# bga_test.net
KiCad netlist of a schematic drawn in EAGLE
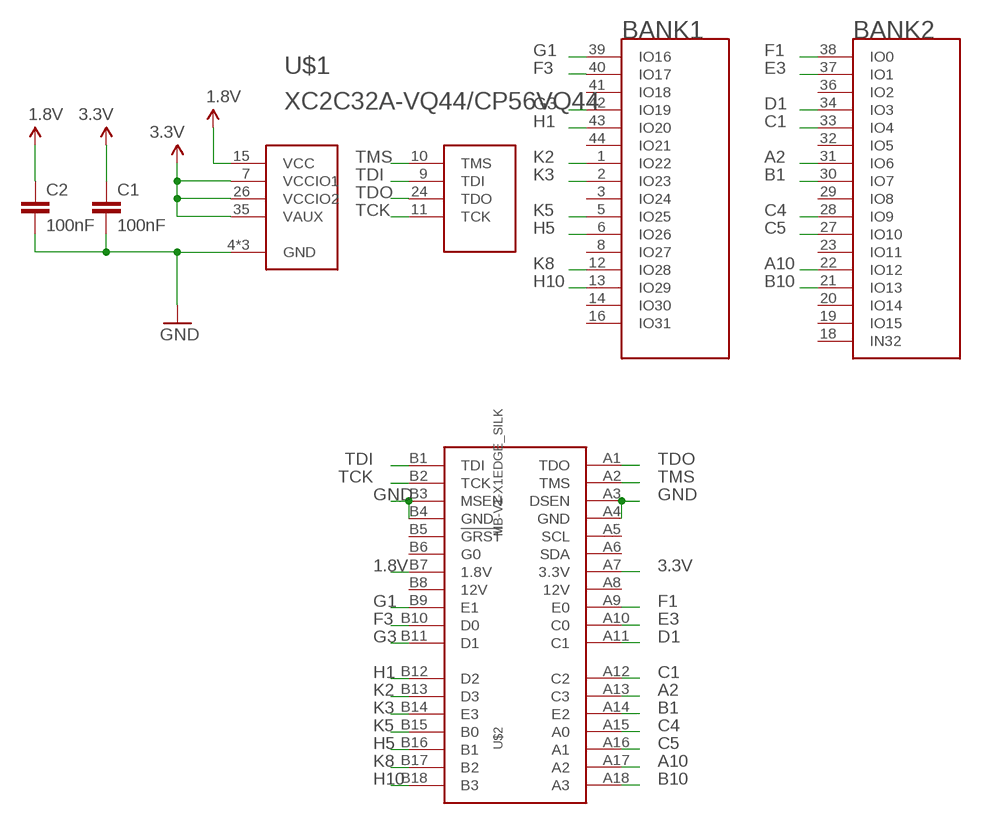
[diagram p0: schematic, sheet 1]

(export (version "E")
  (design (tool "Eeschema 10.0.6"))
  (components
    (comp (ref "C1")
      (value "100nF")
      (footprint "eagle-import:0402-CAP")
      (libsource (lib "eagle-import") (part "CAP0402-CAP"))
    )
    (comp (ref "C2")
      (value "100nF")
      (footprint "eagle-import:0402-CAP")
      (libsource (lib "eagle-import") (part "CAP0402-CAP"))
    )
    (comp (ref "U$1")
      (value "XC2C32A-VQ44/CP56VQ44")
      (footprint "eagle-import:XILINX_VQ44")
      (libsource (lib "eagle-import") (part "XC2C32A-VQ44/CP56VQ44"))
    )
    (comp (ref "U$2")
      (value "MB-V1-X1EDGE_SILK")
      (footprint "eagle-import:MB-V1-X1-EDGE")
      (libsource (lib "eagle-import") (part "MB-V1-X1EDGE_SILK"))
    )
  )
  (nets
    (net (code "1") (name "/A2") (class "Default")
      (node (ref "U$1") (pin "31") (pinfunction "IO6_31") (pintype "bidirectional"))
      (node (ref "U$2") (pin "A13") (pinfunction "C3_A13") (pintype "bidirectional"))
    )
    (net (code "2") (name "/A10") (class "Default")
      (node (ref "U$1") (pin "22") (pinfunction "IO12_22") (pintype "bidirectional"))
      (node (ref "U$2") (pin "A17") (pinfunction "A2_A17") (pintype "bidirectional"))
    )
    (net (code "3") (name "/B1") (class "Default")
      (node (ref "U$1") (pin "30") (pinfunction "IO7_30") (pintype "bidirectional"))
      (node (ref "U$2") (pin "A14") (pinfunction "E2_A14") (pintype "bidirectional"))
    )
    (net (code "4") (name "/B10") (class "Default")
      (node (ref "U$1") (pin "21") (pinfunction "IO13_21") (pintype "bidirectional"))
      (node (ref "U$2") (pin "A18") (pinfunction "A3_A18") (pintype "bidirectional"))
    )
    (net (code "5") (name "/C1") (class "Default")
      (node (ref "U$1") (pin "33") (pinfunction "IO4_33") (pintype "bidirectional"))
      (node (ref "U$2") (pin "A12") (pinfunction "C2_A12") (pintype "bidirectional"))
    )
    (net (code "6") (name "/C4") (class "Default")
      (node (ref "U$1") (pin "28") (pinfunction "IO9_28") (pintype "bidirectional"))
      (node (ref "U$2") (pin "A15") (pinfunction "A0_A15") (pintype "bidirectional"))
    )
    (net (code "7") (name "/C5") (class "Default")
      (node (ref "U$1") (pin "27") (pinfunction "IO10_27") (pintype "bidirectional"))
      (node (ref "U$2") (pin "A16") (pinfunction "A1_A16") (pintype "bidirectional"))
    )
    (net (code "8") (name "/D1") (class "Default")
      (node (ref "U$1") (pin "34") (pinfunction "IO3_34") (pintype "bidirectional"))
      (node (ref "U$2") (pin "A11") (pinfunction "C1_A11") (pintype "bidirectional"))
    )
    (net (code "9") (name "/E3") (class "Default")
      (node (ref "U$1") (pin "37") (pinfunction "IO1_37") (pintype "bidirectional"))
      (node (ref "U$2") (pin "A10") (pinfunction "C0_A10") (pintype "bidirectional"))
    )
    (net (code "10") (name "/F1") (class "Default")
      (node (ref "U$1") (pin "38") (pinfunction "IO0_38") (pintype "bidirectional"))
      (node (ref "U$2") (pin "A9") (pinfunction "E0_A9") (pintype "bidirectional"))
    )
    (net (code "11") (name "/F3") (class "Default")
      (node (ref "U$1") (pin "40") (pinfunction "IO17_40") (pintype "bidirectional"))
      (node (ref "U$2") (pin "B10") (pinfunction "D0_B10") (pintype "bidirectional"))
    )
    (net (code "12") (name "/G1") (class "Default")
      (node (ref "U$1") (pin "39") (pinfunction "IO16_39") (pintype "bidirectional"))
      (node (ref "U$2") (pin "B9") (pinfunction "E1_B9") (pintype "bidirectional"))
    )
    (net (code "13") (name "/G3") (class "Default")
      (node (ref "U$1") (pin "42") (pinfunction "IO19_42") (pintype "bidirectional"))
      (node (ref "U$2") (pin "B11") (pinfunction "D1_B11") (pintype "bidirectional"))
    )
    (net (code "14") (name "/H1") (class "Default")
      (node (ref "U$1") (pin "43") (pinfunction "IO20_43") (pintype "bidirectional"))
      (node (ref "U$2") (pin "B12") (pinfunction "D2_B12") (pintype "bidirectional"))
    )
    (net (code "15") (name "/H5") (class "Default")
      (node (ref "U$1") (pin "6") (pinfunction "IO26_6") (pintype "bidirectional"))
      (node (ref "U$2") (pin "B16") (pinfunction "B1_B16") (pintype "bidirectional"))
    )
    (net (code "16") (name "/H10") (class "Default")
      (node (ref "U$1") (pin "13") (pinfunction "IO29_13") (pintype "bidirectional"))
      (node (ref "U$2") (pin "B18") (pinfunction "B3_B18") (pintype "bidirectional"))
    )
    (net (code "17") (name "/K2") (class "Default")
      (node (ref "U$1") (pin "1") (pinfunction "IO22_1") (pintype "bidirectional"))
      (node (ref "U$2") (pin "B13") (pinfunction "D3_B13") (pintype "bidirectional"))
    )
    (net (code "18") (name "/K3") (class "Default")
      (node (ref "U$1") (pin "2") (pinfunction "IO23_2") (pintype "bidirectional"))
      (node (ref "U$2") (pin "B14") (pinfunction "E3_B14") (pintype "bidirectional"))
    )
    (net (code "19") (name "/K5") (class "Default")
      (node (ref "U$1") (pin "5") (pinfunction "IO25_5") (pintype "bidirectional"))
      (node (ref "U$2") (pin "B15") (pinfunction "B0_B15") (pintype "bidirectional"))
    )
    (net (code "20") (name "/K8") (class "Default")
      (node (ref "U$1") (pin "12") (pinfunction "IO28_12") (pintype "bidirectional"))
      (node (ref "U$2") (pin "B17") (pinfunction "B2_B17") (pintype "bidirectional"))
    )
    (net (code "21") (name "/TCK") (class "Default")
      (node (ref "U$1") (pin "11") (pinfunction "TCK_11") (pintype "bidirectional"))
      (node (ref "U$2") (pin "B2") (pinfunction "TCK_B2") (pintype "bidirectional"))
    )
    (net (code "22") (name "/TDI") (class "Default")
      (node (ref "U$1") (pin "9") (pinfunction "TDI_9") (pintype "bidirectional"))
      (node (ref "U$2") (pin "B1") (pinfunction "TDI_B1") (pintype "bidirectional"))
    )
    (net (code "23") (name "/TDO") (class "Default")
      (node (ref "U$1") (pin "24") (pinfunction "TDO_24") (pintype "bidirectional"))
      (node (ref "U$2") (pin "A1") (pinfunction "TDO_A1") (pintype "bidirectional"))
    )
    (net (code "24") (name "/TMS") (class "Default")
      (node (ref "U$1") (pin "10") (pinfunction "TMS_10") (pintype "bidirectional"))
      (node (ref "U$2") (pin "A2") (pinfunction "TMS_A2") (pintype "bidirectional"))
    )
    (net (code "25") (name "1.8V") (class "Default")
      (node (ref "C2") (pin "1") (pinfunction "1_1") (pintype "passive"))
      (node (ref "U$1") (pin "15") (pinfunction "VCC_15") (pintype "bidirectional"))
      (node (ref "U$2") (pin "B7") (pinfunction "1.8V_B7") (pintype "bidirectional"))
    )
    (net (code "26") (name "3.3V") (class "Default")
      (node (ref "C1") (pin "1") (pinfunction "1_1") (pintype "passive"))
      (node (ref "U$1") (pin "26") (pinfunction "VCCIO2_26") (pintype "bidirectional"))
      (node (ref "U$1") (pin "35") (pinfunction "VAUX_35") (pintype "bidirectional"))
      (node (ref "U$1") (pin "7") (pinfunction "VCCIO1_7") (pintype "bidirectional"))
      (node (ref "U$2") (pin "A7") (pinfunction "3.3V_A7") (pintype "bidirectional"))
    )
    (net (code "27") (name "GND") (class "Default")
      (node (ref "C1") (pin "2") (pinfunction "2_2") (pintype "passive"))
      (node (ref "C2") (pin "2") (pinfunction "2_2") (pintype "passive"))
      (node (ref "U$1") (pin "17") (pinfunction "GND_17") (pintype "bidirectional"))
      (node (ref "U$1") (pin "25") (pinfunction "GND_25") (pintype "bidirectional"))
      (node (ref "U$1") (pin "4") (pinfunction "GND_4") (pintype "bidirectional"))
      (node (ref "U$2") (pin "A3") (pinfunction "DSEN_A3") (pintype "bidirectional"))
      (node (ref "U$2") (pin "A4") (pinfunction "GND_A4") (pintype "bidirectional"))
      (node (ref "U$2") (pin "B3") (pinfunction "MSEN_B3") (pintype "bidirectional"))
      (node (ref "U$2") (pin "B4") (pinfunction "GND_B4") (pintype "bidirectional"))
    )
    (net (code "28") (name "unconnected-(U$1-IN32-Pad18)") (class "Default")
      (node (ref "U$1") (pin "18") (pinfunction "IN32_18") (pintype "bidirectional"))
    )
    (net (code "29") (name "unconnected-(U$1-IO2-Pad36)") (class "Default")
      (node (ref "U$1") (pin "36") (pinfunction "IO2_36") (pintype "bidirectional"))
    )
    (net (code "30") (name "unconnected-(U$1-IO5-Pad32)") (class "Default")
      (node (ref "U$1") (pin "32") (pinfunction "IO5_32") (pintype "bidirectional"))
    )
    (net (code "31") (name "unconnected-(U$1-IO8-Pad29)") (class "Default")
      (node (ref "U$1") (pin "29") (pinfunction "IO8_29") (pintype "bidirectional"))
    )
    (net (code "32") (name "unconnected-(U$1-IO11-Pad23)") (class "Default")
      (node (ref "U$1") (pin "23") (pinfunction "IO11_23") (pintype "bidirectional"))
    )
    (net (code "33") (name "unconnected-(U$1-IO14-Pad20)") (class "Default")
      (node (ref "U$1") (pin "20") (pinfunction "IO14_20") (pintype "bidirectional"))
    )
    (net (code "34") (name "unconnected-(U$1-IO15-Pad19)") (class "Default")
      (node (ref "U$1") (pin "19") (pinfunction "IO15_19") (pintype "bidirectional"))
    )
    (net (code "35") (name "unconnected-(U$1-IO18-Pad41)") (class "Default")
      (node (ref "U$1") (pin "41") (pinfunction "IO18_41") (pintype "bidirectional"))
    )
    (net (code "36") (name "unconnected-(U$1-IO21-Pad44)") (class "Default")
      (node (ref "U$1") (pin "44") (pinfunction "IO21_44") (pintype "bidirectional"))
    )
    (net (code "37") (name "unconnected-(U$1-IO24-Pad3)") (class "Default")
      (node (ref "U$1") (pin "3") (pinfunction "IO24_3") (pintype "bidirectional"))
    )
    (net (code "38") (name "unconnected-(U$1-IO27-Pad8)") (class "Default")
      (node (ref "U$1") (pin "8") (pinfunction "IO27_8") (pintype "bidirectional"))
    )
    (net (code "39") (name "unconnected-(U$1-IO30-Pad14)") (class "Default")
      (node (ref "U$1") (pin "14") (pinfunction "IO30_14") (pintype "bidirectional"))
    )
    (net (code "40") (name "unconnected-(U$1-IO31-Pad16)") (class "Default")
      (node (ref "U$1") (pin "16") (pinfunction "IO31_16") (pintype "bidirectional"))
    )
    (net (code "41") (name "unconnected-(U$2-12V-PadA8)") (class "Default")
      (node (ref "U$2") (pin "A8") (pinfunction "12V_A8") (pintype "bidirectional"))
    )
    (net (code "42") (name "unconnected-(U$2-12V-PadB8)") (class "Default")
      (node (ref "U$2") (pin "B8") (pinfunction "12V_B8") (pintype "bidirectional"))
    )
    (net (code "43") (name "unconnected-(U$2-G0-PadB6)") (class "Default")
      (node (ref "U$2") (pin "B6") (pinfunction "G0_B6") (pintype "bidirectional"))
    )
    (net (code "44") (name "unconnected-(U$2-SCL-PadA5)") (class "Default")
      (node (ref "U$2") (pin "A5") (pinfunction "SCL_A5") (pintype "bidirectional"))
    )
    (net (code "45") (name "unconnected-(U$2-SDA-PadA6)") (class "Default")
      (node (ref "U$2") (pin "A6") (pinfunction "SDA_A6") (pintype "bidirectional"))
    )
    (net (code "46") (name "unconnected-(U$2-~{GRST}-PadB5)") (class "Default")
      (node (ref "U$2") (pin "B5") (pinfunction "~{GRST}_B5") (pintype "bidirectional"))
    )
  )
)
